# 01_MAIN.net
KiCad netlist of a schematic drawn in Altium Designer
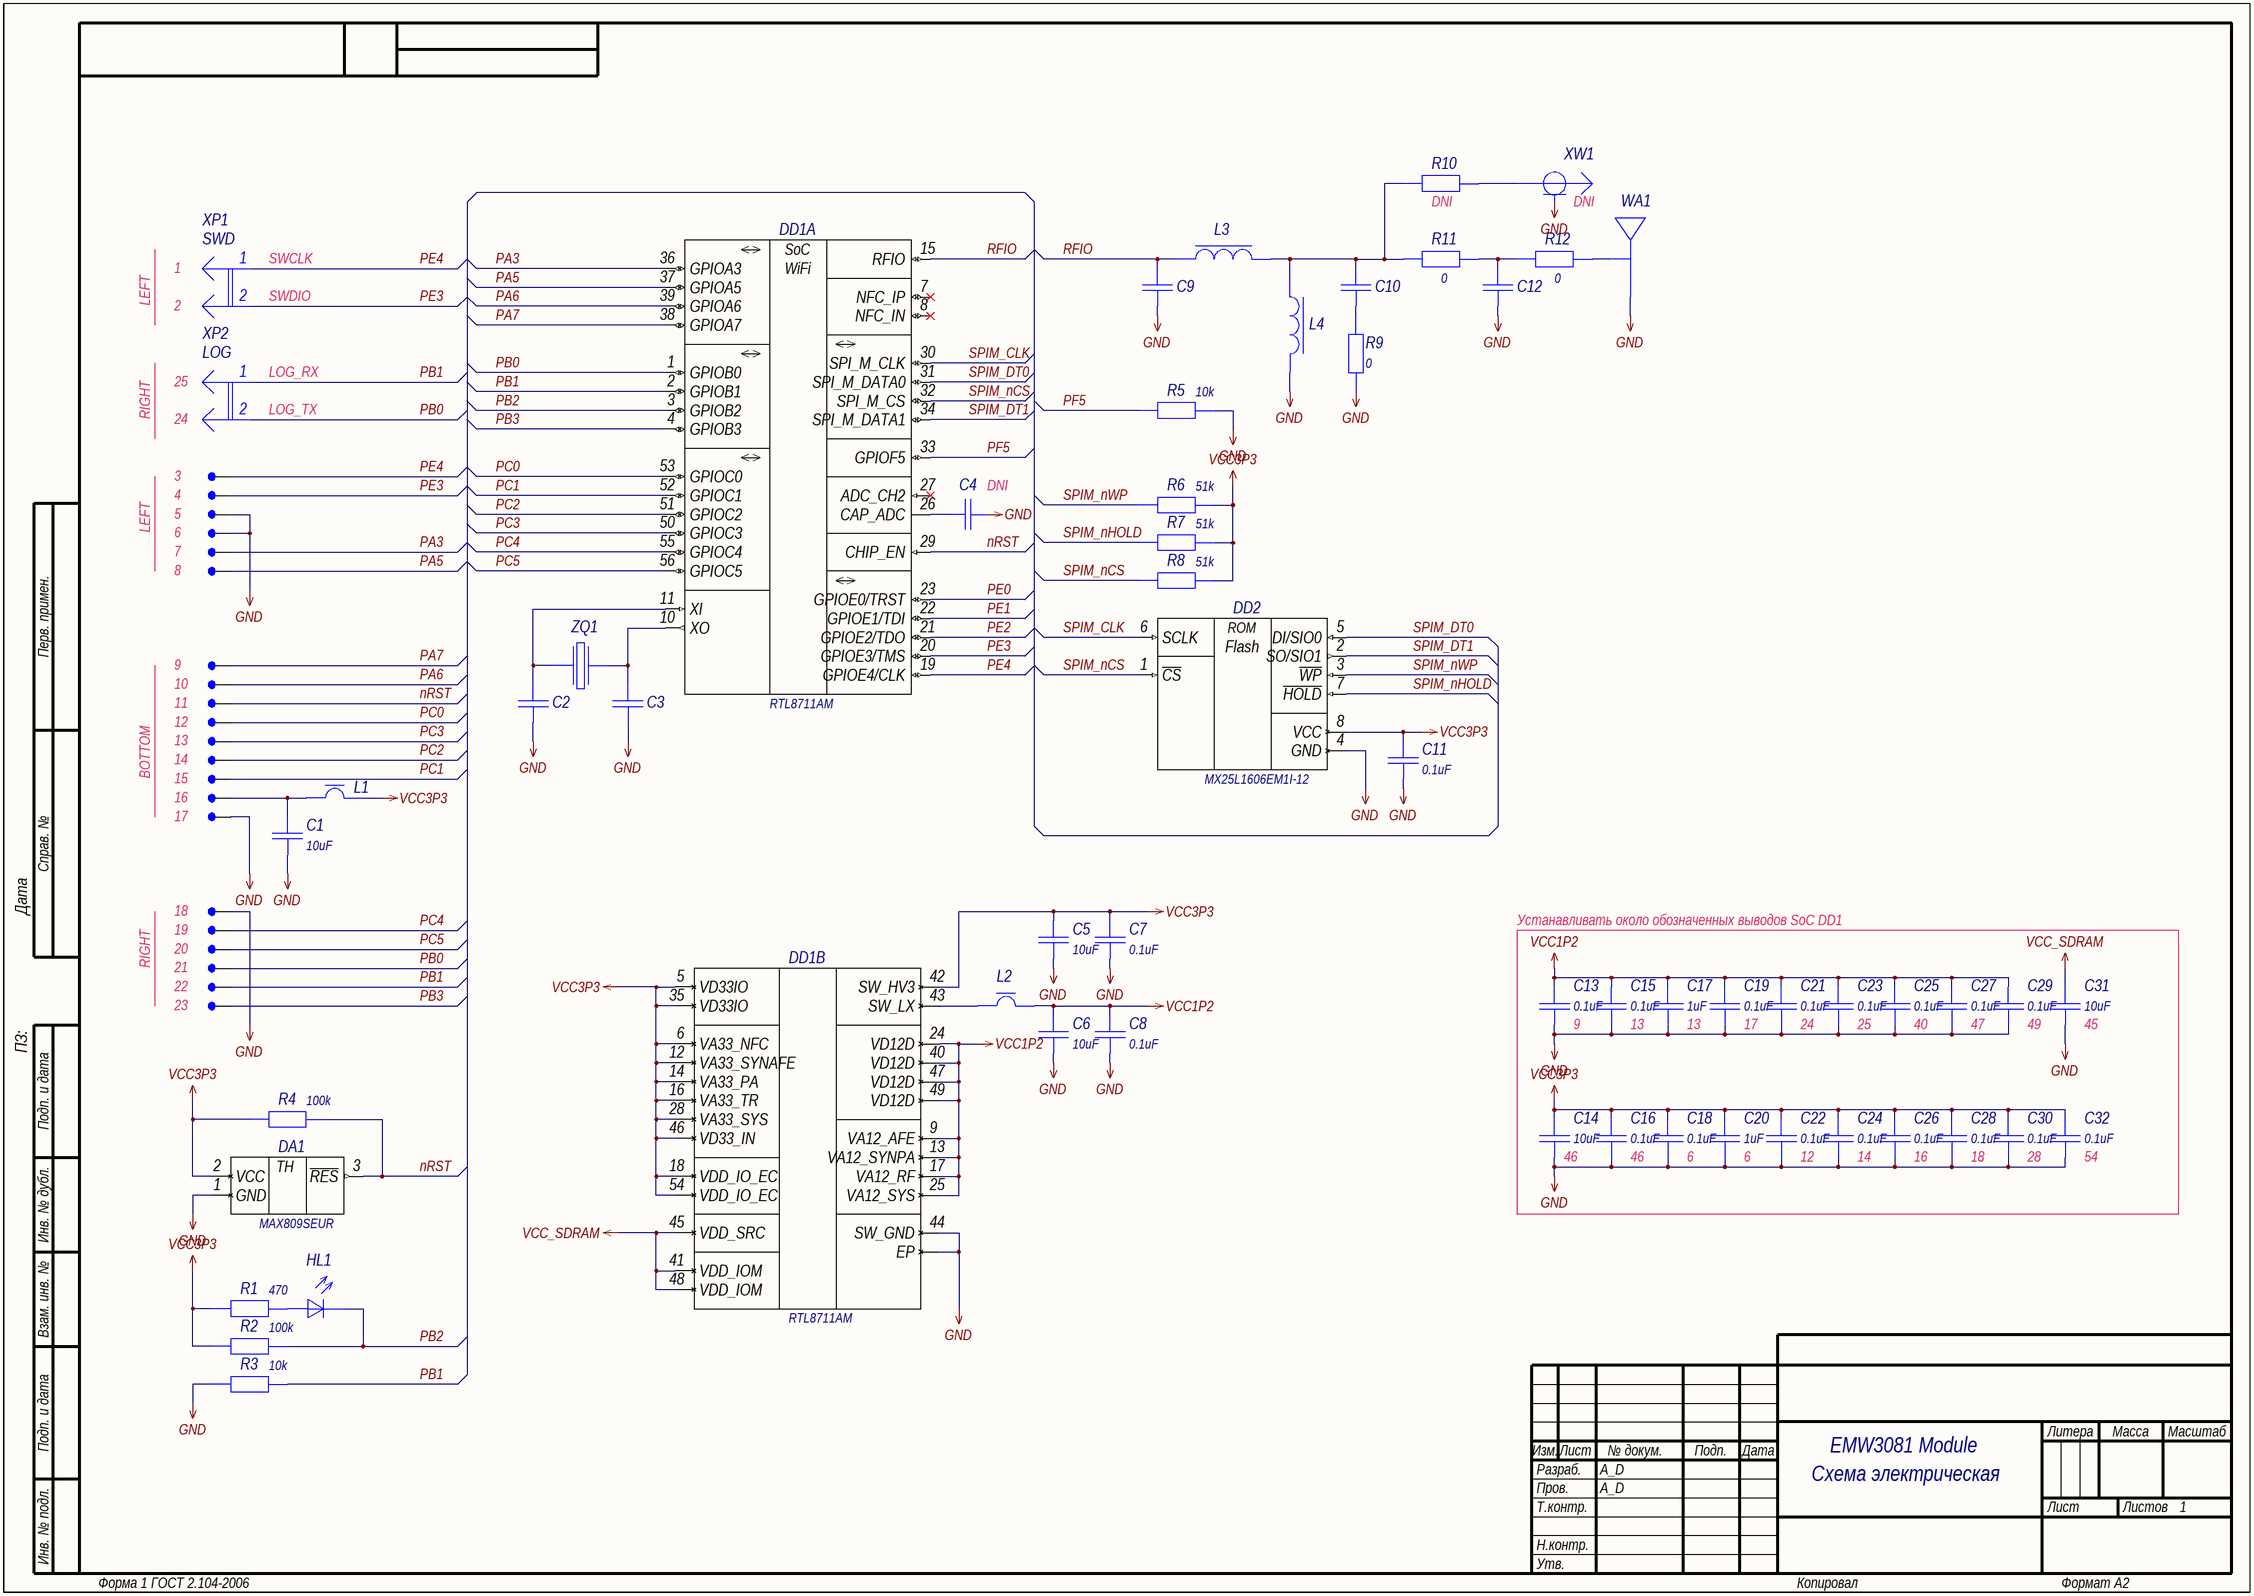
[diagram p0: 01_MAIN.SchDoc]

(export (version "E")
  (design (tool "Eeschema 10.0.6"))
  (components
    (comp (ref "C1")
      (value "10uF")
      (footprint "C0603_L")
      (fields
        (field (name "PART NUMBER") "GRM188R60J106ME47D")
        (field (name "VOLTAGE") "6.3V")
        (field (name "TOLERANCE") "±20%")
        (field (name "PUBLISHER") "Andrew Danich")
      )
      (libsource (lib "Lib_IMP_GOST") (part "Capacitor"))
    )
    (comp (ref "C2")
      (value "Capacitor")
      (footprint "C0402_L")
      (fields
        (field (name "PART NUMBER") "GRM1555C1H120JA01D")
        (field (name "VOLTAGE") "50V")
        (field (name "TOLERANCE") "±5%")
        (field (name "PUBLISHER") "Andrew Danich")
      )
      (libsource (lib "Lib_IMP_GOST") (part "Capacitor"))
    )
    (comp (ref "C3")
      (value "Capacitor")
      (footprint "C0402_L")
      (fields
        (field (name "PART NUMBER") "GRM1555C1H120JA01D")
        (field (name "VOLTAGE") "50V")
        (field (name "TOLERANCE") "±5%")
        (field (name "PUBLISHER") "Andrew Danich")
      )
      (libsource (lib "Lib_IMP_GOST") (part "Capacitor"))
    )
    (comp (ref "C4")
      (value "Capacitor")
      (footprint "C0603_L")
      (fields
        (field (name "PART NUMBER") "GRM188R60J106ME47D")
        (field (name "VOLTAGE") "6.3V")
        (field (name "TOLERANCE") "±20%")
        (field (name "PUBLISHER") "Andrew Danich")
      )
      (libsource (lib "Lib_IMP_GOST") (part "Capacitor"))
    )
    (comp (ref "C5")
      (value "10uF")
      (footprint "C0603_L")
      (fields
        (field (name "PART NUMBER") "GRM188R60J106ME47D")
        (field (name "VOLTAGE") "6.3V")
        (field (name "TOLERANCE") "±20%")
        (field (name "PUBLISHER") "Andrew Danich")
      )
      (libsource (lib "Lib_IMP_GOST") (part "Capacitor"))
    )
    (comp (ref "C6")
      (value "10uF")
      (footprint "C0603_L")
      (fields
        (field (name "PART NUMBER") "GRM188R60J106ME47D")
        (field (name "VOLTAGE") "6.3V")
        (field (name "TOLERANCE") "±20%")
        (field (name "PUBLISHER") "Andrew Danich")
      )
      (libsource (lib "Lib_IMP_GOST") (part "Capacitor"))
    )
    (comp (ref "C7")
      (value "0.1uF")
      (footprint "C0402_L")
      (fields
        (field (name "PART NUMBER") "GRM155R71A104KA01D")
        (field (name "VOLTAGE") "10V")
        (field (name "TOLERANCE") "±10%")
        (field (name "PUBLISHER") "Andrew Danich")
      )
      (libsource (lib "Lib_IMP_GOST") (part "Capacitor"))
    )
    (comp (ref "C8")
      (value "0.1uF")
      (footprint "C0402_L")
      (fields
        (field (name "PART NUMBER") "GRM155R71A104KA01D")
        (field (name "VOLTAGE") "10V")
        (field (name "TOLERANCE") "±10%")
        (field (name "PUBLISHER") "Andrew Danich")
      )
      (libsource (lib "Lib_IMP_GOST") (part "Capacitor"))
    )
    (comp (ref "C9")
      (value "Capacitor")
      (footprint "C0402_L")
      (fields
        (field (name "PART NUMBER") "GRM1555C1E2R7BA01D")
        (field (name "VOLTAGE") "50V")
        (field (name "TOLERANCE") "±0.1pF")
        (field (name "PUBLISHER") "Andrew Danich")
      )
      (libsource (lib "Lib_IMP_GOST") (part "Capacitor"))
    )
    (comp (ref "C10")
      (value "Capacitor")
      (footprint "C0402_L")
      (fields
        (field (name "PART NUMBER") "GRM1555C1E2R7BA01D")
        (field (name "VOLTAGE") "50V")
        (field (name "TOLERANCE") "±0.1pF")
        (field (name "PUBLISHER") "Andrew Danich")
      )
      (libsource (lib "Lib_IMP_GOST") (part "Capacitor"))
    )
    (comp (ref "C11")
      (value "0.1uF")
      (footprint "C0402_L")
      (fields
        (field (name "PART NUMBER") "GRM155R71A104KA01D")
        (field (name "VOLTAGE") "10V")
        (field (name "TOLERANCE") "±10%")
        (field (name "PUBLISHER") "Andrew Danich")
      )
      (libsource (lib "Lib_IMP_GOST") (part "Capacitor"))
    )
    (comp (ref "C12")
      (value "Capacitor")
      (footprint "C0402_L")
      (fields
        (field (name "PART NUMBER") "GRM1555C1E2R7BA01D")
        (field (name "VOLTAGE") "50V")
        (field (name "TOLERANCE") "±0.1pF")
        (field (name "PUBLISHER") "Andrew Danich")
      )
      (libsource (lib "Lib_IMP_GOST") (part "Capacitor"))
    )
    (comp (ref "C13")
      (value "0.1uF")
      (footprint "C0402_L")
      (fields
        (field (name "PART NUMBER") "GRM155R71A104KA01D")
        (field (name "VOLTAGE") "10V")
        (field (name "TOLERANCE") "±10%")
        (field (name "PUBLISHER") "Andrew Danich")
      )
      (libsource (lib "Lib_IMP_GOST") (part "Capacitor"))
    )
    (comp (ref "C14")
      (value "10uF")
      (footprint "C0603_L")
      (fields
        (field (name "PART NUMBER") "GRM188R60J106ME47D")
        (field (name "VOLTAGE") "6.3V")
        (field (name "TOLERANCE") "±20%")
        (field (name "PUBLISHER") "Andrew Danich")
      )
      (libsource (lib "Lib_IMP_GOST") (part "Capacitor"))
    )
    (comp (ref "C15")
      (value "0.1uF")
      (footprint "C0402_L")
      (fields
        (field (name "PART NUMBER") "GRM155R71A104KA01D")
        (field (name "VOLTAGE") "10V")
        (field (name "TOLERANCE") "±10%")
        (field (name "PUBLISHER") "Andrew Danich")
      )
      (libsource (lib "Lib_IMP_GOST") (part "Capacitor"))
    )
    (comp (ref "C16")
      (value "0.1uF")
      (footprint "C0402_L")
      (fields
        (field (name "PART NUMBER") "GRM155R71A104KA01D")
        (field (name "VOLTAGE") "10V")
        (field (name "TOLERANCE") "±10%")
        (field (name "PUBLISHER") "Andrew Danich")
      )
      (libsource (lib "Lib_IMP_GOST") (part "Capacitor"))
    )
    (comp (ref "C17")
      (value "1uF")
      (footprint "C0402_L")
      (fields
        (field (name "PART NUMBER") "GRM155R61A105KE15D")
        (field (name "VOLTAGE") "10V")
        (field (name "TOLERANCE") "±10%")
        (field (name "PUBLISHER") "Andrew Danich")
      )
      (libsource (lib "Lib_IMP_GOST") (part "Capacitor"))
    )
    (comp (ref "C18")
      (value "0.1uF")
      (footprint "C0402_L")
      (fields
        (field (name "PART NUMBER") "GRM155R71A104KA01D")
        (field (name "VOLTAGE") "10V")
        (field (name "TOLERANCE") "±10%")
        (field (name "PUBLISHER") "Andrew Danich")
      )
      (libsource (lib "Lib_IMP_GOST") (part "Capacitor"))
    )
    (comp (ref "C19")
      (value "0.1uF")
      (footprint "C0402_L")
      (fields
        (field (name "PART NUMBER") "GRM155R71A104KA01D")
        (field (name "VOLTAGE") "10V")
        (field (name "TOLERANCE") "±10%")
        (field (name "PUBLISHER") "Andrew Danich")
      )
      (libsource (lib "Lib_IMP_GOST") (part "Capacitor"))
    )
    (comp (ref "C20")
      (value "1uF")
      (footprint "C0402_L")
      (fields
        (field (name "PART NUMBER") "GRM155R61A105KE15D")
        (field (name "VOLTAGE") "10V")
        (field (name "TOLERANCE") "±10%")
        (field (name "PUBLISHER") "Andrew Danich")
      )
      (libsource (lib "Lib_IMP_GOST") (part "Capacitor"))
    )
    (comp (ref "C21")
      (value "0.1uF")
      (footprint "C0402_L")
      (fields
        (field (name "PART NUMBER") "GRM155R71A104KA01D")
        (field (name "VOLTAGE") "10V")
        (field (name "TOLERANCE") "±10%")
        (field (name "PUBLISHER") "Andrew Danich")
      )
      (libsource (lib "Lib_IMP_GOST") (part "Capacitor"))
    )
    (comp (ref "C22")
      (value "0.1uF")
      (footprint "C0402_L")
      (fields
        (field (name "PART NUMBER") "GRM155R71A104KA01D")
        (field (name "VOLTAGE") "10V")
        (field (name "TOLERANCE") "±10%")
        (field (name "PUBLISHER") "Andrew Danich")
      )
      (libsource (lib "Lib_IMP_GOST") (part "Capacitor"))
    )
    (comp (ref "C23")
      (value "0.1uF")
      (footprint "C0402_L")
      (fields
        (field (name "PART NUMBER") "GRM155R71A104KA01D")
        (field (name "VOLTAGE") "10V")
        (field (name "TOLERANCE") "±10%")
        (field (name "PUBLISHER") "Andrew Danich")
      )
      (libsource (lib "Lib_IMP_GOST") (part "Capacitor"))
    )
    (comp (ref "C24")
      (value "0.1uF")
      (footprint "C0402_L")
      (fields
        (field (name "PART NUMBER") "GRM155R71A104KA01D")
        (field (name "VOLTAGE") "10V")
        (field (name "TOLERANCE") "±10%")
        (field (name "PUBLISHER") "Andrew Danich")
      )
      (libsource (lib "Lib_IMP_GOST") (part "Capacitor"))
    )
    (comp (ref "C25")
      (value "0.1uF")
      (footprint "C0402_L")
      (fields
        (field (name "PART NUMBER") "GRM155R71A104KA01D")
        (field (name "VOLTAGE") "10V")
        (field (name "TOLERANCE") "±10%")
        (field (name "PUBLISHER") "Andrew Danich")
      )
      (libsource (lib "Lib_IMP_GOST") (part "Capacitor"))
    )
    (comp (ref "C26")
      (value "0.1uF")
      (footprint "C0402_L")
      (fields
        (field (name "PART NUMBER") "GRM155R71A104KA01D")
        (field (name "VOLTAGE") "10V")
        (field (name "TOLERANCE") "±10%")
        (field (name "PUBLISHER") "Andrew Danich")
      )
      (libsource (lib "Lib_IMP_GOST") (part "Capacitor"))
    )
    (comp (ref "C27")
      (value "0.1uF")
      (footprint "C0402_L")
      (fields
        (field (name "PART NUMBER") "GRM155R71A104KA01D")
        (field (name "VOLTAGE") "10V")
        (field (name "TOLERANCE") "±10%")
        (field (name "PUBLISHER") "Andrew Danich")
      )
      (libsource (lib "Lib_IMP_GOST") (part "Capacitor"))
    )
    (comp (ref "C28")
      (value "0.1uF")
      (footprint "C0402_L")
      (fields
        (field (name "PART NUMBER") "GRM155R71A104KA01D")
        (field (name "VOLTAGE") "10V")
        (field (name "TOLERANCE") "±10%")
        (field (name "PUBLISHER") "Andrew Danich")
      )
      (libsource (lib "Lib_IMP_GOST") (part "Capacitor"))
    )
    (comp (ref "C29")
      (value "0.1uF")
      (footprint "C0402_L")
      (fields
        (field (name "PART NUMBER") "GRM155R71A104KA01D")
        (field (name "VOLTAGE") "10V")
        (field (name "TOLERANCE") "±10%")
        (field (name "PUBLISHER") "Andrew Danich")
      )
      (libsource (lib "Lib_IMP_GOST") (part "Capacitor"))
    )
    (comp (ref "C30")
      (value "0.1uF")
      (footprint "C0402_L")
      (fields
        (field (name "PART NUMBER") "GRM155R71A104KA01D")
        (field (name "VOLTAGE") "10V")
        (field (name "TOLERANCE") "±10%")
        (field (name "PUBLISHER") "Andrew Danich")
      )
      (libsource (lib "Lib_IMP_GOST") (part "Capacitor"))
    )
    (comp (ref "C31")
      (value "10uF")
      (footprint "C0603_L")
      (fields
        (field (name "PART NUMBER") "GRM188R60J106ME47D")
        (field (name "VOLTAGE") "6.3V")
        (field (name "TOLERANCE") "±20%")
        (field (name "PUBLISHER") "Andrew Danich")
      )
      (libsource (lib "Lib_IMP_GOST") (part "Capacitor"))
    )
    (comp (ref "C32")
      (value "0.1uF")
      (footprint "C0402_L")
      (fields
        (field (name "PART NUMBER") "GRM155R71A104KA01D")
        (field (name "VOLTAGE") "10V")
        (field (name "TOLERANCE") "±10%")
        (field (name "PUBLISHER") "Andrew Danich")
      )
      (libsource (lib "Lib_IMP_GOST") (part "Capacitor"))
    )
    (comp (ref "DA1")
      (value "MAX809SEUR")
      (footprint "SOT-23")
      (fields
        (field (name "MANUFACTURER") "Maxim Integrated")
        (field (name "Comment") "MAX809-Series")
        (field (name "PUBLISHER") "Andrew Danich")
      )
      (libsource (lib "Lib_IMP_GOST") (part "MAX809-Series"))
    )
    (comp (ref "DD1")
      (value "RTL8711AM")
      (footprint "QFN-56-7x7")
      (fields (field (name "MANUFACTURER") "Realtek") (field (name "PUBLISHER") "Andrew Danich"))
      (libsource (lib "Lib_IMP_GOST") (part "RTL8711AM"))
    )
    (comp (ref "DD2")
      (value "MX25L1606EM1I-12")
      (footprint "SOIC-8")
      (fields
        (field (name "MANUFACTURER") "MXIC")
        (field (name "Comment") "MX25L1606E-8Pin-Series")
        (field (name "PUBLISHER") "Andrew Danich")
      )
      (libsource (lib "Lib_IMP_GOST") (part "MX25L1606E-8Pin-Series"))
    )
    (comp (ref "HL1")
      (value "Text")
      (footprint "LD0603_L")
      (fields (field (name "PART NUMBER") "BL-LS0603GC") (field (name "PUBLISHER") "Andrew Danich"))
      (libsource (lib "Lib_IMP_GOST") (part "Led-1"))
    )
    (comp (ref "L1")
      (value "FerriteBead")
      (footprint "L0603_L")
      (fields
        (field (name "PART NUMBER") "BLM18PG121SN1")
        (field (name "MANUFACTURER") "Murata")
        (field (name "PUBLISHER") "Andrew Danich")
      )
      (libsource (lib "Lib_IMP_GOST") (part "FerriteBead"))
    )
    (comp (ref "L2")
      (value "FerriteBead")
      (footprint "L0805_L")
      (fields
        (field (name "PART NUMBER") "BLM21PG331SN1")
        (field (name "MANUFACTURER") "Murata")
        (field (name "PUBLISHER") "Andrew Danich")
      )
      (libsource (lib "Lib_IMP_GOST") (part "FerriteBead"))
    )
    (comp (ref "L3")
      (value "Coil")
      (footprint "L0402_L")
      (fields
        (field (name "PART NUMBER") "LQG15HS2N2S02D")
        (field (name "TOLERANCE") "±0.3nH")
        (field (name "MANUFACTURER") "Murata")
        (field (name "PUBLISHER") "Andrew Danich")
      )
      (libsource (lib "Lib_IMP_GOST") (part "Coil"))
    )
    (comp (ref "L4")
      (value "Coil")
      (footprint "L0402_L")
      (fields
        (field (name "PART NUMBER") "LQG15HS2N2S02D")
        (field (name "TOLERANCE") "±0.3nH")
        (field (name "MANUFACTURER") "Murata")
        (field (name "PUBLISHER") "Andrew Danich")
      )
      (libsource (lib "Lib_IMP_GOST") (part "Coil"))
    )
    (comp (ref "R1")
      (value "470")
      (footprint "R0402_L")
      (fields
        (field (name "PART NUMBER") "RC0402JR-07430RL")
        (field (name "TOLERANCE") "±5%")
        (field (name "MANUFACTURER") "Yageo")
        (field (name "PUBLISHER") "Andrew Danich")
      )
      (libsource (lib "Lib_IMP_GOST") (part "Resistor"))
    )
    (comp (ref "R2")
      (value "100k")
      (footprint "R0402_L")
      (fields
        (field (name "PART NUMBER") "RC0402JR-07100KL")
        (field (name "TOLERANCE") "±5%")
        (field (name "MANUFACTURER") "Yageo")
        (field (name "PUBLISHER") "Andrew Danich")
      )
      (libsource (lib "Lib_IMP_GOST") (part "Resistor"))
    )
    (comp (ref "R3")
      (value "10k")
      (footprint "R0402_L")
      (fields
        (field (name "PART NUMBER") "RC0402FR-0710KL")
        (field (name "TOLERANCE") "±1%")
        (field (name "MANUFACTURER") "Yageo")
        (field (name "PUBLISHER") "Andrew Danich")
      )
      (libsource (lib "Lib_IMP_GOST") (part "Resistor"))
    )
    (comp (ref "R4")
      (value "100k")
      (footprint "R0402_L")
      (fields
        (field (name "PART NUMBER") "RC0402JR-07100KL")
        (field (name "TOLERANCE") "±5%")
        (field (name "MANUFACTURER") "Yageo")
        (field (name "PUBLISHER") "Andrew Danich")
      )
      (libsource (lib "Lib_IMP_GOST") (part "Resistor"))
    )
    (comp (ref "R5")
      (value "10k")
      (footprint "R0402_L")
      (fields
        (field (name "PART NUMBER") "RC0402FR-0710KL")
        (field (name "TOLERANCE") "±1%")
        (field (name "MANUFACTURER") "Yageo")
        (field (name "PUBLISHER") "Andrew Danich")
      )
      (libsource (lib "Lib_IMP_GOST") (part "Resistor"))
    )
    (comp (ref "R6")
      (value "51k")
      (footprint "R0402_L")
      (fields
        (field (name "PART NUMBER") "RC0402JR-0751KL")
        (field (name "TOLERANCE") "±5%")
        (field (name "MANUFACTURER") "Yageo")
        (field (name "PUBLISHER") "Andrew Danich")
      )
      (libsource (lib "Lib_IMP_GOST") (part "Resistor"))
    )
    (comp (ref "R7")
      (value "51k")
      (footprint "R0402_L")
      (fields
        (field (name "PART NUMBER") "RC0402JR-0751KL")
        (field (name "TOLERANCE") "±5%")
        (field (name "MANUFACTURER") "Yageo")
        (field (name "PUBLISHER") "Andrew Danich")
      )
      (libsource (lib "Lib_IMP_GOST") (part "Resistor"))
    )
    (comp (ref "R8")
      (value "51k")
      (footprint "R0402_L")
      (fields
        (field (name "PART NUMBER") "RC0402JR-0751KL")
        (field (name "TOLERANCE") "±5%")
        (field (name "MANUFACTURER") "Yageo")
        (field (name "PUBLISHER") "Andrew Danich")
      )
      (libsource (lib "Lib_IMP_GOST") (part "Resistor"))
    )
    (comp (ref "R9")
      (value "0")
      (footprint "R0402_L")
      (fields
        (field (name "PART NUMBER") "RC0402JR-070RL")
        (field (name "TOLERANCE") "±1%")
        (field (name "MANUFACTURER") "Yageo")
        (field (name "PUBLISHER") "Andrew Danich")
      )
      (libsource (lib "Lib_IMP_GOST") (part "Resistor"))
    )
    (comp (ref "R10")
      (value "Resistor")
      (footprint "R0402_L")
      (fields
        (field (name "PART NUMBER") "RC0402JR-070RL")
        (field (name "TOLERANCE") "±1%")
        (field (name "MANUFACTURER") "Yageo")
        (field (name "PUBLISHER") "Andrew Danich")
      )
      (libsource (lib "Lib_IMP_GOST") (part "Resistor"))
    )
    (comp (ref "R11")
      (value "0")
      (footprint "R0402_L")
      (fields
        (field (name "PART NUMBER") "RC0402JR-070RL")
        (field (name "TOLERANCE") "±1%")
        (field (name "MANUFACTURER") "Yageo")
        (field (name "PUBLISHER") "Andrew Danich")
      )
      (libsource (lib "Lib_IMP_GOST") (part "Resistor"))
    )
    (comp (ref "R12")
      (value "0")
      (footprint "R0402_L")
      (fields
        (field (name "PART NUMBER") "RC0402JR-070RL")
        (field (name "TOLERANCE") "±1%")
        (field (name "MANUFACTURER") "Yageo")
        (field (name "PUBLISHER") "Andrew Danich")
      )
      (libsource (lib "Lib_IMP_GOST") (part "Resistor"))
    )
    (comp (ref "WA1")
      (value "Antenna_PCB_2p")
      (footprint "PCB-AN043")
      (fields
        (field (name "PART NUMBER") "PCB-AN043")
        (field (name "MANUFACTURER") "Texas Instruments")
        (field (name "PUBLISHER") "Andrew Danich")
      )
      (libsource (lib "Lib_IMP_GOST") (part "Antenna_PCB_2p"))
    )
    (comp (ref "XP1")
      (value "SWD")
      (footprint "PLS-2")
      (fields (field (name "PART NUMBER") "PLS-2") (field (name "PUBLISHER") "Andrew Danich"))
      (libsource (lib "Lib_IMP_GOST") (part "Con-2-M"))
    )
    (comp (ref "XP2")
      (value "LOG")
      (footprint "PLS-2")
      (fields (field (name "PART NUMBER") "PLS-2") (field (name "PUBLISHER") "Andrew Danich"))
      (libsource (lib "Lib_IMP_GOST") (part "Con-2-M"))
    )
    (comp (ref "XS1") (value "PCB-SPIN") (footprint "PCB-SPIN") (libsource (lib "Schlib") (part "PCB-SPIN")))
    (comp (ref "XS2") (value "PCB-SPIN") (footprint "PCB-SPIN") (libsource (lib "Schlib") (part "PCB-SPIN")))
    (comp (ref "XS3") (value "PCB-SPIN") (footprint "PCB-SPIN") (libsource (lib "Schlib") (part "PCB-SPIN")))
    (comp (ref "XS4") (value "PCB-SPIN") (footprint "PCB-SPIN") (libsource (lib "Schlib") (part "PCB-SPIN")))
    (comp (ref "XS5") (value "PCB-SPIN") (footprint "PCB-SPIN") (libsource (lib "Schlib") (part "PCB-SPIN")))
    (comp (ref "XS6") (value "PCB-SPIN") (footprint "PCB-SPIN") (libsource (lib "Schlib") (part "PCB-SPIN")))
    (comp (ref "XS7") (value "PCB-SPIN") (footprint "PCB-SPIN") (libsource (lib "Schlib") (part "PCB-SPIN")))
    (comp (ref "XS8") (value "PCB-SPIN") (footprint "PCB-SPIN") (libsource (lib "Schlib") (part "PCB-SPIN")))
    (comp (ref "XS9") (value "PCB-SPIN") (footprint "PCB-SPIN") (libsource (lib "Schlib") (part "PCB-SPIN")))
    (comp (ref "XS10") (value "PCB-SPIN") (footprint "PCB-SPIN") (libsource (lib "Schlib") (part "PCB-SPIN")))
    (comp (ref "XS11") (value "PCB-SPIN") (footprint "PCB-SPIN") (libsource (lib "Schlib") (part "PCB-SPIN")))
    (comp (ref "XS12") (value "PCB-SPIN") (footprint "PCB-SPIN") (libsource (lib "Schlib") (part "PCB-SPIN")))
    (comp (ref "XS13") (value "PCB-SPIN") (footprint "PCB-SPIN") (libsource (lib "Schlib") (part "PCB-SPIN")))
    (comp (ref "XS14") (value "PCB-SPIN") (footprint "PCB-SPIN") (libsource (lib "Schlib") (part "PCB-SPIN")))
    (comp (ref "XS15") (value "PCB-SPIN") (footprint "PCB-SPIN") (libsource (lib "Schlib") (part "PCB-SPIN")))
    (comp (ref "XS16") (value "PCB-SPIN") (footprint "PCB-SPIN") (libsource (lib "Schlib") (part "PCB-SPIN")))
    (comp (ref "XS17") (value "PCB-SPIN") (footprint "PCB-SPIN") (libsource (lib "Schlib") (part "PCB-SPIN")))
    (comp (ref "XS18") (value "PCB-SPIN") (footprint "PCB-SPIN") (libsource (lib "Schlib") (part "PCB-SPIN")))
    (comp (ref "XS19") (value "PCB-SPIN") (footprint "PCB-SPIN") (libsource (lib "Schlib") (part "PCB-SPIN")))
    (comp (ref "XS20") (value "PCB-SPIN") (footprint "PCB-SPIN") (libsource (lib "Schlib") (part "PCB-SPIN")))
    (comp (ref "XS21") (value "PCB-SPIN") (footprint "PCB-SPIN") (libsource (lib "Schlib") (part "PCB-SPIN")))
    (comp (ref "XW1")
      (value "Con-RF-M")
      (footprint "1909763-1")
      (fields
        (field (name "PART NUMBER") "1909763-1")
        (field (name "MANUFACTURER") "TE Connectivity")
        (field (name "PUBLISHER") "НТЦ \"Вектор\"")
      )
      (libsource (lib "Lib_IMP_GOST") (part "Con-RF-M"))
    )
    (comp (ref "ZQ1")
      (value "Crystal")
      (footprint "SX-2520")
      (fields
        (field (name "PART NUMBER") "CX2520DB40000D0FLJCC")
        (field (name "MANUFACTURER") "AVX / Kyocera")
        (field (name "PUBLISHER") "Andrew Danich")
      )
      (libsource (lib "Lib_IMP_GOST") (part "Crystal"))
    )
  )
  (nets
    (net (code "1") (name "/PA3") (class "Default")
      (node (ref "DD1") (pin "36") (pinfunction "GPIOA3_36") (pintype "bidirectional"))
      (node (ref "XS5") (pin "1") (pinfunction "1_1") (pintype "passive"))
    )
    (net (code "2") (name "/PA5") (class "Default")
      (node (ref "DD1") (pin "37") (pinfunction "GPIOA5_37") (pintype "bidirectional"))
      (node (ref "XS6") (pin "1") (pinfunction "1_1") (pintype "passive"))
    )
    (net (code "3") (name "/PA6") (class "Default")
      (node (ref "DD1") (pin "39") (pinfunction "GPIOA6_39") (pintype "bidirectional"))
      (node (ref "XS8") (pin "1") (pinfunction "1_1") (pintype "passive"))
    )
    (net (code "4") (name "/PA7") (class "Default")
      (node (ref "DD1") (pin "38") (pinfunction "GPIOA7_38") (pintype "bidirectional"))
      (node (ref "XS7") (pin "1") (pinfunction "1_1") (pintype "passive"))
    )
    (net (code "5") (name "/PB0") (class "Default")
      (node (ref "DD1") (pin "1") (pinfunction "GPIOB0_1") (pintype "bidirectional"))
      (node (ref "XP2") (pin "2") (pintype "passive"))
      (node (ref "XS19") (pin "1") (pinfunction "1_1") (pintype "passive"))
    )
    (net (code "6") (name "/PB1") (class "Default")
      (node (ref "DD1") (pin "2") (pinfunction "GPIOB1_2") (pintype "bidirectional"))
      (node (ref "R3") (pin "2") (pinfunction "2_2") (pintype "passive"))
      (node (ref "XP2") (pin "1") (pintype "passive"))
      (node (ref "XS20") (pin "1") (pinfunction "1_1") (pintype "passive"))
    )
    (net (code "7") (name "/PB2") (class "Default")
      (node (ref "DD1") (pin "3") (pinfunction "GPIOB2_3") (pintype "bidirectional"))
      (node (ref "HL1") (pin "2") (pinfunction "К_2") (pintype "passive"))
      (node (ref "R2") (pin "2") (pinfunction "2_2") (pintype "passive"))
    )
    (net (code "8") (name "/PB3") (class "Default")
      (node (ref "DD1") (pin "4") (pinfunction "GPIOB3_4") (pintype "bidirectional"))
      (node (ref "XS21") (pin "1") (pinfunction "1_1") (pintype "passive"))
    )
    (net (code "9") (name "/PC0") (class "Default")
      (node (ref "DD1") (pin "53") (pinfunction "GPIOC0_53") (pintype "bidirectional"))
      (node (ref "XS10") (pin "1") (pinfunction "1_1") (pintype "passive"))
    )
    (net (code "10") (name "/PC1") (class "Default")
      (node (ref "DD1") (pin "52") (pinfunction "GPIOC1_52") (pintype "bidirectional"))
      (node (ref "XS13") (pin "1") (pinfunction "1_1") (pintype "passive"))
    )
    (net (code "11") (name "/PC2") (class "Default")
      (node (ref "DD1") (pin "51") (pinfunction "GPIOC2_51") (pintype "bidirectional"))
      (node (ref "XS12") (pin "1") (pinfunction "1_1") (pintype "passive"))
    )
    (net (code "12") (name "/PC3") (class "Default")
      (node (ref "DD1") (pin "50") (pinfunction "GPIOC3_50") (pintype "bidirectional"))
      (node (ref "XS11") (pin "1") (pinfunction "1_1") (pintype "passive"))
    )
    (net (code "13") (name "/PC4") (class "Default")
      (node (ref "DD1") (pin "55") (pinfunction "GPIOC4_55") (pintype "bidirectional"))
      (node (ref "XS17") (pin "1") (pinfunction "1_1") (pintype "passive"))
    )
    (net (code "14") (name "/PC5") (class "Default")
      (node (ref "DD1") (pin "56") (pinfunction "GPIOC5_56") (pintype "bidirectional"))
      (node (ref "XS18") (pin "1") (pinfunction "1_1") (pintype "passive"))
    )
    (net (code "15") (name "/PE0") (class "Default")
      (node (ref "DD1") (pin "23") (pinfunction "GPIOE0/TRST_23") (pintype "bidirectional"))
    )
    (net (code "16") (name "/PE1") (class "Default")
      (node (ref "DD1") (pin "22") (pinfunction "GPIOE1/TDI_22") (pintype "bidirectional"))
    )
    (net (code "17") (name "/PE2") (class "Default")
      (node (ref "DD1") (pin "21") (pinfunction "GPIOE2/TDO_21") (pintype "bidirectional"))
    )
    (net (code "18") (name "/PE3") (class "Default")
      (node (ref "DD1") (pin "20") (pinfunction "GPIOE3/TMS_20") (pintype "bidirectional"))
      (node (ref "XP1") (pin "2") (pintype "passive"))
      (node (ref "XS2") (pin "1") (pinfunction "1_1") (pintype "passive"))
    )
    (net (code "19") (name "/PE4") (class "Default")
      (node (ref "DD1") (pin "19") (pinfunction "GPIOE4/CLK_19") (pintype "bidirectional"))
      (node (ref "XP1") (pin "1") (pintype "passive"))
      (node (ref "XS1") (pin "1") (pinfunction "1_1") (pintype "passive"))
    )
    (net (code "20") (name "/PF5") (class "Default")
      (node (ref "DD1") (pin "33") (pinfunction "GPIOF5_33") (pintype "bidirectional"))
      (node (ref "R5") (pin "1") (pinfunction "1_1") (pintype "passive"))
    )
    (net (code "21") (name "/RFIO") (class "Default")
      (node (ref "C9") (pin "2") (pinfunction "2_2") (pintype "passive"))
      (node (ref "DD1") (pin "15") (pinfunction "RFIO_15") (pintype "bidirectional"))
      (node (ref "L3") (pin "1") (pinfunction "1_1") (pintype "passive"))
    )
    (net (code "22") (name "/SPIM_CLK") (class "Default")
      (node (ref "DD1") (pin "30") (pinfunction "SPI_M_CLK_30") (pintype "bidirectional"))
      (node (ref "DD2") (pin "6") (pinfunction "SCLK_6") (pintype "input"))
    )
    (net (code "23") (name "/SPIM_DT0") (class "Default")
      (node (ref "DD1") (pin "31") (pinfunction "SPI_M_DATA0_31") (pintype "bidirectional"))
      (node (ref "DD2") (pin "5") (pinfunction "DI/SIO0_5") (pintype "input"))
    )
    (net (code "24") (name "/SPIM_DT1") (class "Default")
      (node (ref "DD1") (pin "34") (pinfunction "SPI_M_DATA1_34") (pintype "bidirectional"))
      (node (ref "DD2") (pin "2") (pinfunction "SO/SIO1_2") (pintype "output"))
    )
    (net (code "25") (name "/SPIM_nCS") (class "Default")
      (node (ref "DD1") (pin "32") (pinfunction "SPI_M_CS_32") (pintype "bidirectional"))
      (node (ref "DD2") (pin "1") (pinfunction "~{CS}_1") (pintype "input"))
      (node (ref "R8") (pin "2") (pinfunction "2_2") (pintype "passive"))
    )
    (net (code "26") (name "/SPIM_nHOLD") (class "Default")
      (node (ref "DD2") (pin "7") (pinfunction "~{HOLD}_7") (pintype "input"))
      (node (ref "R7") (pin "2") (pinfunction "2_2") (pintype "passive"))
    )
    (net (code "27") (name "/SPIM_nWP") (class "Default")
      (node (ref "DD2") (pin "3") (pinfunction "~{WP}_3") (pintype "input"))
      (node (ref "R6") (pin "2") (pinfunction "2_2") (pintype "passive"))
    )
    (net (code "28") (name "/nRST") (class "Default")
      (node (ref "DA1") (pin "3") (pinfunction "~{RES}_3") (pintype "output"))
      (node (ref "DD1") (pin "29") (pinfunction "CHIP_EN_29") (pintype "input"))
      (node (ref "R4") (pin "2") (pinfunction "2_2") (pintype "passive"))
      (node (ref "XS9") (pin "1") (pinfunction "1_1") (pintype "passive"))
    )
    (net (code "29") (name "GND") (class "Default")
      (node (ref "C1") (pin "1") (pinfunction "1_1") (pintype "passive"))
      (node (ref "C11") (pin "1") (pinfunction "1_1") (pintype "passive"))
      (node (ref "C12") (pin "1") (pinfunction "1_1") (pintype "passive"))
      (node (ref "C13") (pin "1") (pinfunction "1_1") (pintype "passive"))
      (node (ref "C14") (pin "1") (pinfunction "1_1") (pintype "passive"))
      (node (ref "C15") (pin "1") (pinfunction "1_1") (pintype "passive"))
      (node (ref "C16") (pin "1") (pinfunction "1_1") (pintype "passive"))
      (node (ref "C17") (pin "1") (pinfunction "1_1") (pintype "passive"))
      (node (ref "C18") (pin "1") (pinfunction "1_1") (pintype "passive"))
      (node (ref "C19") (pin "1") (pinfunction "1_1") (pintype "passive"))
      (node (ref "C2") (pin "1") (pinfunction "1_1") (pintype "passive"))
      (node (ref "C20") (pin "1") (pinfunction "1_1") (pintype "passive"))
      (node (ref "C21") (pin "1") (pinfunction "1_1") (pintype "passive"))
      (node (ref "C22") (pin "1") (pinfunction "1_1") (pintype "passive"))
      (node (ref "C23") (pin "1") (pinfunction "1_1") (pintype "passive"))
      (node (ref "C24") (pin "1") (pinfunction "1_1") (pintype "passive"))
      (node (ref "C25") (pin "1") (pinfunction "1_1") (pintype "passive"))
      (node (ref "C26") (pin "1") (pinfunction "1_1") (pintype "passive"))
      (node (ref "C27") (pin "1") (pinfunction "1_1") (pintype "passive"))
      (node (ref "C28") (pin "1") (pinfunction "1_1") (pintype "passive"))
      (node (ref "C29") (pin "1") (pinfunction "1_1") (pintype "passive"))
      (node (ref "C3") (pin "1") (pinfunction "1_1") (pintype "passive"))
      (node (ref "C30") (pin "1") (pinfunction "1_1") (pintype "passive"))
      (node (ref "C31") (pin "1") (pinfunction "1_1") (pintype "passive"))
      (node (ref "C32") (pin "1") (pinfunction "1_1") (pintype "passive"))
      (node (ref "C4") (pin "1") (pinfunction "1_1") (pintype "passive"))
      (node (ref "C5") (pin "1") (pinfunction "1_1") (pintype "passive"))
      (node (ref "C6") (pin "1") (pinfunction "1_1") (pintype "passive"))
      (node (ref "C7") (pin "1") (pinfunction "1_1") (pintype "passive"))
      (node (ref "C8") (pin "1") (pinfunction "1_1") (pintype "passive"))
      (node (ref "C9") (pin "1") (pinfunction "1_1") (pintype "passive"))
      (node (ref "DA1") (pin "1") (pinfunction "GND_1") (pintype "power_in"))
      (node (ref "DD1") (pin "44") (pinfunction "SW_GND_44") (pintype "power_in"))
      (node (ref "DD1") (pin "57") (pinfunction "EP_57") (pintype "power_in"))
      (node (ref "DD2") (pin "4") (pinfunction "GND_4") (pintype "power_in"))
      (node (ref "L4") (pin "2") (pinfunction "2_2") (pintype "passive"))
      (node (ref "R3") (pin "1") (pinfunction "1_1") (pintype "passive"))
      (node (ref "R5") (pin "2") (pinfunction "2_2") (pintype "passive"))
      (node (ref "R9") (pin "1") (pinfunction "1_1") (pintype "passive"))
      (node (ref "WA1") (pin "2") (pinfunction "2_2") (pintype "passive"))
      (node (ref "XS15") (pin "1") (pinfunction "1_1") (pintype "passive"))
      (node (ref "XS16") (pin "1") (pinfunction "1_1") (pintype "passive"))
      (node (ref "XS3") (pin "1") (pinfunction "1_1") (pintype "passive"))
      (node (ref "XS4") (pin "1") (pinfunction "1_1") (pintype "passive"))
      (node (ref "XW1") (pin "2") (pintype "passive"))
    )
    (net (code "30") (name "Net-(C1-Pad2)") (class "Default")
      (node (ref "C1") (pin "2") (pinfunction "2_2") (pintype "passive"))
      (node (ref "L1") (pin "1") (pinfunction "1_1") (pintype "passive"))
      (node (ref "XS14") (pin "1") (pinfunction "1_1") (pintype "passive"))
    )
    (net (code "31") (name "Net-(C10-Pad1)") (class "Default")
      (node (ref "C10") (pin "1") (pinfunction "1_1") (pintype "passive"))
      (node (ref "R9") (pin "2") (pinfunction "2_2") (pintype "passive"))
    )
    (net (code "32") (name "Net-(C10-Pad2)") (class "Default")
      (node (ref "C10") (pin "2") (pinfunction "2_2") (pintype "passive"))
      (node (ref "L3") (pin "2") (pinfunction "2_2") (pintype "passive"))
      (node (ref "L4") (pin "1") (pinfunction "1_1") (pintype "passive"))
      (node (ref "R10") (pin "2") (pinfunction "2_2") (pintype "passive"))
      (node (ref "R11") (pin "2") (pinfunction "2_2") (pintype "passive"))
    )
    (net (code "33") (name "Net-(C12-Pad2)") (class "Default")
      (node (ref "C12") (pin "2") (pinfunction "2_2") (pintype "passive"))
      (node (ref "R11") (pin "1") (pinfunction "1_1") (pintype "passive"))
      (node (ref "R12") (pin "2") (pinfunction "2_2") (pintype "passive"))
    )
    (net (code "34") (name "Net-(DD1A-CAP_ADC)") (class "Default")
      (node (ref "C4") (pin "2") (pinfunction "2_2") (pintype "passive"))
      (node (ref "DD1") (pin "26") (pinfunction "CAP_ADC_26") (pintype "passive"))
    )
    (net (code "35") (name "Net-(DD1A-XI)") (class "Default")
      (node (ref "C2") (pin "2") (pinfunction "2_2") (pintype "passive"))
      (node (ref "DD1") (pin "11") (pinfunction "XI_11") (pintype "input"))
      (node (ref "ZQ1") (pin "1") (pinfunction "1_1") (pintype "passive"))
    )
    (net (code "36") (name "Net-(DD1A-XO)") (class "Default")
      (node (ref "C3") (pin "2") (pinfunction "2_2") (pintype "passive"))
      (node (ref "DD1") (pin "10") (pinfunction "XO_10") (pintype "output"))
      (node (ref "ZQ1") (pin "3") (pinfunction "3_3") (pintype "passive"))
    )
    (net (code "37") (name "Net-(DD1B-SW_LX)") (class "Default")
      (node (ref "DD1") (pin "43") (pinfunction "SW_LX_43") (pintype "power_in"))
      (node (ref "L2") (pin "1") (pinfunction "1_1") (pintype "passive"))
    )
    (net (code "38") (name "Net-(HL1-А)") (class "Default")
      (node (ref "HL1") (pin "1") (pinfunction "А_1") (pintype "passive"))
      (node (ref "R1") (pin "2") (pinfunction "2_2") (pintype "passive"))
    )
    (net (code "39") (name "Net-(R10-Pad1)") (class "Default")
      (node (ref "R10") (pin "1") (pinfunction "1_1") (pintype "passive"))
      (node (ref "XW1") (pin "1") (pintype "passive"))
    )
    (net (code "40") (name "Net-(R12-Pad1)") (class "Default")
      (node (ref "R12") (pin "1") (pinfunction "1_1") (pintype "passive"))
      (node (ref "WA1") (pin "1") (pinfunction "1_1") (pintype "passive"))
    )
    (net (code "41") (name "VCC1P2") (class "Default")
      (node (ref "C13") (pin "2") (pinfunction "2_2") (pintype "passive"))
      (node (ref "C15") (pin "2") (pinfunction "2_2") (pintype "passive"))
      (node (ref "C17") (pin "2") (pinfunction "2_2") (pintype "passive"))
      (node (ref "C19") (pin "2") (pinfunction "2_2") (pintype "passive"))
      (node (ref "C21") (pin "2") (pinfunction "2_2") (pintype "passive"))
      (node (ref "C23") (pin "2") (pinfunction "2_2") (pintype "passive"))
      (node (ref "C25") (pin "2") (pinfunction "2_2") (pintype "passive"))
      (node (ref "C27") (pin "2") (pinfunction "2_2") (pintype "passive"))
      (node (ref "C29") (pin "2") (pinfunction "2_2") (pintype "passive"))
      (node (ref "C6") (pin "2") (pinfunction "2_2") (pintype "passive"))
      (node (ref "C8") (pin "2") (pinfunction "2_2") (pintype "passive"))
      (node (ref "DD1") (pin "13") (pinfunction "VA12_SYNPA_13") (pintype "power_in"))
      (node (ref "DD1") (pin "17") (pinfunction "VA12_RF_17") (pintype "power_in"))
      (node (ref "DD1") (pin "24") (pinfunction "VD12D_24") (pintype "power_in"))
      (node (ref "DD1") (pin "25") (pinfunction "VA12_SYS_25") (pintype "power_in"))
      (node (ref "DD1") (pin "40") (pinfunction "VD12D_40") (pintype "power_in"))
      (node (ref "DD1") (pin "47") (pinfunction "VD12D_47") (pintype "power_in"))
      (node (ref "DD1") (pin "49") (pinfunction "VD12D_49") (pintype "power_in"))
      (node (ref "DD1") (pin "9") (pinfunction "VA12_AFE_9") (pintype "power_in"))
      (node (ref "L2") (pin "2") (pinfunction "2_2") (pintype "passive"))
    )
    (net (code "42") (name "VCC3P3") (class "Default")
      (node (ref "C11") (pin "2") (pinfunction "2_2") (pintype "passive"))
      (node (ref "C14") (pin "2") (pinfunction "2_2") (pintype "passive"))
      (node (ref "C16") (pin "2") (pinfunction "2_2") (pintype "passive"))
      (node (ref "C18") (pin "2") (pinfunction "2_2") (pintype "passive"))
      (node (ref "C20") (pin "2") (pinfunction "2_2") (pintype "passive"))
      (node (ref "C22") (pin "2") (pinfunction "2_2") (pintype "passive"))
      (node (ref "C24") (pin "2") (pinfunction "2_2") (pintype "passive"))
      (node (ref "C26") (pin "2") (pinfunction "2_2") (pintype "passive"))
      (node (ref "C28") (pin "2") (pinfunction "2_2") (pintype "passive"))
      (node (ref "C30") (pin "2") (pinfunction "2_2") (pintype "passive"))
      (node (ref "C32") (pin "2") (pinfunction "2_2") (pintype "passive"))
      (node (ref "C5") (pin "2") (pinfunction "2_2") (pintype "passive"))
      (node (ref "C7") (pin "2") (pinfunction "2_2") (pintype "passive"))
      (node (ref "DA1") (pin "2") (pinfunction "VCC_2") (pintype "power_in"))
      (node (ref "DD1") (pin "12") (pinfunction "VA33_SYNAFE_12") (pintype "power_in"))
      (node (ref "DD1") (pin "14") (pinfunction "VA33_PA_14") (pintype "power_in"))
      (node (ref "DD1") (pin "16") (pinfunction "VA33_TR_16") (pintype "power_in"))
      (node (ref "DD1") (pin "18") (pinfunction "VDD_IO_EC_18") (pintype "power_in"))
      (node (ref "DD1") (pin "28") (pinfunction "VA33_SYS_28") (pintype "power_in"))
      (node (ref "DD1") (pin "35") (pinfunction "VD33IO_35") (pintype "power_in"))
      (node (ref "DD1") (pin "42") (pinfunction "SW_HV3_42") (pintype "power_in"))
      (node (ref "DD1") (pin "46") (pinfunction "VD33_IN_46") (pintype "power_in"))
      (node (ref "DD1") (pin "5") (pinfunction "VD33IO_5") (pintype "power_in"))
      (node (ref "DD1") (pin "54") (pinfunction "VDD_IO_EC_54") (pintype "power_in"))
      (node (ref "DD1") (pin "6") (pinfunction "VA33_NFC_6") (pintype "power_in"))
      (node (ref "DD2") (pin "8") (pinfunction "VCC_8") (pintype "power_in"))
      (node (ref "L1") (pin "2") (pinfunction "2_2") (pintype "passive"))
      (node (ref "R1") (pin "1") (pinfunction "1_1") (pintype "passive"))
      (node (ref "R2") (pin "1") (pinfunction "1_1") (pintype "passive"))
      (node (ref "R4") (pin "1") (pinfunction "1_1") (pintype "passive"))
      (node (ref "R6") (pin "1") (pinfunction "1_1") (pintype "passive"))
      (node (ref "R7") (pin "1") (pinfunction "1_1") (pintype "passive"))
      (node (ref "R8") (pin "1") (pinfunction "1_1") (pintype "passive"))
    )
    (net (code "43") (name "VCC_SDRAM") (class "Default")
      (node (ref "C31") (pin "2") (pinfunction "2_2") (pintype "passive"))
      (node (ref "DD1") (pin "41") (pinfunction "VDD_IOM_41") (pintype "power_in"))
      (node (ref "DD1") (pin "45") (pinfunction "VDD_SRC_45") (pintype "power_in"))
      (node (ref "DD1") (pin "48") (pinfunction "VDD_IOM_48") (pintype "power_in"))
    )
    (net (code "44") (name "unconnected-(DD1A-ADC_CH2-Pad27)") (class "Default")
      (node (ref "DD1") (pin "27") (pinfunction "ADC_CH2_27") (pintype "input+no_connect"))
    )
    (net (code "45") (name "unconnected-(DD1A-NFC_IN-Pad8)") (class "Default")
      (node (ref "DD1") (pin "8") (pinfunction "NFC_IN_8") (pintype "bidirectional+no_connect"))
    )
    (net (code "46") (name "unconnected-(DD1A-NFC_IP-Pad7)") (class "Default")
      (node (ref "DD1") (pin "7") (pinfunction "NFC_IP_7") (pintype "bidirectional+no_connect"))
    )
  )
)
